# main.net
KiCad netlist of a schematic drawn in EAGLE
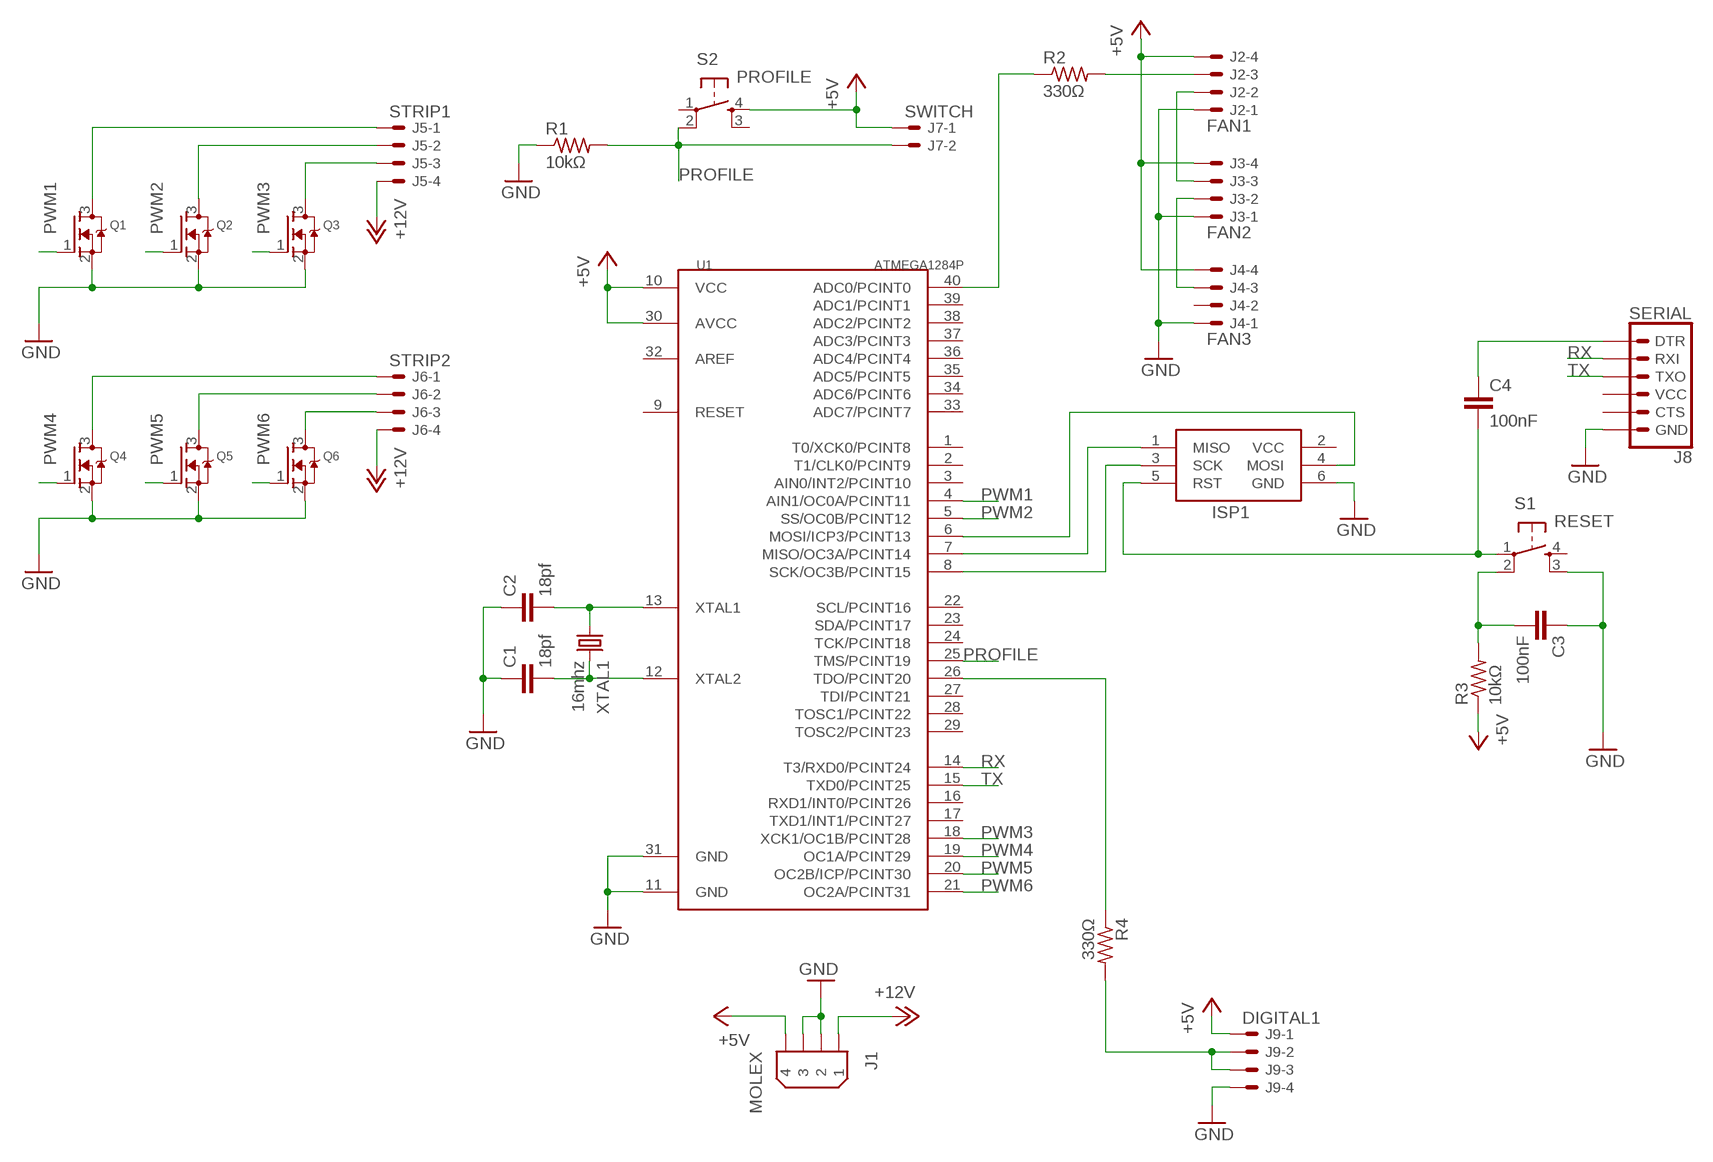
[diagram p0: schematic, sheet 1]

(export (version "E")
  (design (tool "Eeschema 10.0.6"))
  (components
    (comp (ref "C1")
      (value "18pf")
      (footprint "eagle-import:C0805")
      (libsource (lib "eagle-import") (part "C"))
    )
    (comp (ref "C2")
      (value "18pf")
      (footprint "eagle-import:C0805")
      (libsource (lib "eagle-import") (part "C"))
    )
    (comp (ref "C3")
      (value "100nF")
      (footprint "eagle-import:C0805")
      (libsource (lib "eagle-import") (part "C-EUC0805"))
    )
    (comp (ref "C4")
      (value "100nF")
      (footprint "eagle-import:C0805")
      (libsource (lib "eagle-import") (part "C-EUC0805"))
    )
    (comp (ref "ISP1")
      (value "AVRISP-6")
      (footprint "eagle-import:AVRISP")
      (libsource (lib "eagle-import") (part "AVRISP-6"))
    )
    (comp (ref "J1")
      (value "MOLEX")
      (footprint "eagle-import:9090-4R")
      (libsource (lib "eagle-import") (part "9090-4R"))
    )
    (comp (ref "J2")
      (value "FAN1")
      (footprint "eagle-import:22-23-2041")
      (fields (field (name "MF") "MOLEX") (field (name "MPN") "22-23-2041"))
      (libsource (lib "eagle-import") (part "22-23-2041"))
    )
    (comp (ref "J3")
      (value "FAN2")
      (footprint "eagle-import:22-23-2041")
      (fields (field (name "MF") "MOLEX") (field (name "MPN") "22-23-2041"))
      (libsource (lib "eagle-import") (part "22-23-2041"))
    )
    (comp (ref "J4")
      (value "FAN3")
      (footprint "eagle-import:22-23-2041")
      (fields (field (name "MF") "MOLEX") (field (name "MPN") "22-23-2041"))
      (libsource (lib "eagle-import") (part "22-23-2041"))
    )
    (comp (ref "J5")
      (value "STRIP1")
      (footprint "eagle-import:22-23-2041")
      (fields (field (name "MF") "MOLEX") (field (name "MPN") "22-23-2041"))
      (libsource (lib "eagle-import") (part "22-23-2041"))
    )
    (comp (ref "J6")
      (value "STRIP2")
      (footprint "eagle-import:22-23-2041")
      (fields (field (name "MF") "MOLEX") (field (name "MPN") "22-23-2041"))
      (libsource (lib "eagle-import") (part "22-23-2041"))
    )
    (comp (ref "J7")
      (value "SWITCH")
      (footprint "eagle-import:22-23-2021")
      (fields (field (name "MF") "MOLEX") (field (name "MPN") "22-23-2021"))
      (libsource (lib "eagle-import") (part "22-23-2021"))
    )
    (comp (ref "J8")
      (value "SERIAL")
      (footprint "eagle-import:1X06")
      (libsource (lib "eagle-import") (part "6_PIN_SERIAL_TARGET"))
    )
    (comp (ref "J9")
      (value "DIGITAL1")
      (footprint "eagle-import:22-23-2041")
      (fields (field (name "MF") "MOLEX") (field (name "MPN") "22-23-2041"))
      (libsource (lib "eagle-import") (part "22-23-2041"))
    )
    (comp (ref "Q1")
      (value "MOSFET-NREFLOW")
      (footprint "eagle-import:SOT23")
      (libsource (lib "eagle-import") (part "MOSFET-NREFLOW"))
    )
    (comp (ref "Q2")
      (value "MOSFET-NREFLOW")
      (footprint "eagle-import:SOT23")
      (libsource (lib "eagle-import") (part "MOSFET-NREFLOW"))
    )
    (comp (ref "Q3")
      (value "MOSFET-NREFLOW")
      (footprint "eagle-import:SOT23")
      (libsource (lib "eagle-import") (part "MOSFET-NREFLOW"))
    )
    (comp (ref "Q4")
      (value "MOSFET-NREFLOW")
      (footprint "eagle-import:SOT23")
      (libsource (lib "eagle-import") (part "MOSFET-NREFLOW"))
    )
    (comp (ref "Q5")
      (value "MOSFET-NREFLOW")
      (footprint "eagle-import:SOT23")
      (libsource (lib "eagle-import") (part "MOSFET-NREFLOW"))
    )
    (comp (ref "Q6")
      (value "MOSFET-NREFLOW")
      (footprint "eagle-import:SOT23")
      (libsource (lib "eagle-import") (part "MOSFET-NREFLOW"))
    )
    (comp (ref "R1")
      (value "10kΩ")
      (footprint "eagle-import:M0805")
      (libsource (lib "eagle-import") (part "R-US_M0805"))
    )
    (comp (ref "R2")
      (value "330Ω")
      (footprint "eagle-import:M0805")
      (libsource (lib "eagle-import") (part "R-US_M0805"))
    )
    (comp (ref "R3")
      (value "10kΩ")
      (footprint "eagle-import:M0805")
      (libsource (lib "eagle-import") (part "R-US_M0805"))
    )
    (comp (ref "R4")
      (value "330Ω")
      (footprint "eagle-import:M0805")
      (libsource (lib "eagle-import") (part "R-US_M0805"))
    )
    (comp (ref "S1")
      (value "RESET")
      (footprint "eagle-import:B3F-1000")
      (libsource (lib "eagle-import") (part "BUTTON"))
    )
    (comp (ref "S2")
      (value "PROFILE")
      (footprint "eagle-import:B3F-1000")
      (libsource (lib "eagle-import") (part "BUTTON"))
    )
    (comp (ref "U1")
      (value "ATMEGA1284P")
      (footprint "eagle-import:DIL40")
      (libsource (lib "eagle-import") (part "MEGA1284P"))
    )
    (comp (ref "XTAL1")
      (value "16mhz")
      (footprint "eagle-import:HC49U-V")
      (libsource (lib "eagle-import") (part "CRYSTALHC49U-V"))
    )
  )
  (nets
    (net (code "1") (name "+5V") (class "Default")
      (node (ref "J1") (pin "4") (pinfunction "4_4") (pintype "passive"))
      (node (ref "J2") (pin "4") (pinfunction "S_4") (pintype "passive"))
      (node (ref "J3") (pin "4") (pinfunction "S_4") (pintype "passive"))
      (node (ref "J4") (pin "4") (pinfunction "S_4") (pintype "passive"))
      (node (ref "J7") (pin "1") (pinfunction "S_1") (pintype "passive"))
      (node (ref "J9") (pin "1") (pinfunction "S_1") (pintype "passive"))
      (node (ref "R3") (pin "1") (pinfunction "1_1") (pintype "passive"))
      (node (ref "S2") (pin "4") (pinfunction "S_4") (pintype "passive"))
      (node (ref "U1") (pin "10") (pinfunction "VCC_10") (pintype "bidirectional"))
      (node (ref "U1") (pin "30") (pinfunction "AVCC_30") (pintype "bidirectional"))
    )
    (net (code "2") (name "+12V") (class "Default")
      (node (ref "J1") (pin "1") (pinfunction "1_1") (pintype "passive"))
      (node (ref "J5") (pin "4") (pinfunction "S_4") (pintype "passive"))
      (node (ref "J6") (pin "4") (pinfunction "S_4") (pintype "passive"))
    )
    (net (code "3") (name "/PROFILE") (class "Default")
      (node (ref "J7") (pin "2") (pinfunction "S_2") (pintype "passive"))
      (node (ref "R1") (pin "2") (pinfunction "2_2") (pintype "passive"))
      (node (ref "S2") (pin "2") (pinfunction "P1_2") (pintype "passive"))
      (node (ref "U1") (pin "25") (pinfunction "TMS/PCINT19_25") (pintype "bidirectional"))
    )
    (net (code "4") (name "/PWM1") (class "Default")
      (node (ref "Q1") (pin "1") (pinfunction "G_1") (pintype "bidirectional"))
      (node (ref "U1") (pin "4") (pinfunction "AIN1/OC0A/PCINT11_4") (pintype "bidirectional"))
    )
    (net (code "5") (name "/PWM2") (class "Default")
      (node (ref "Q2") (pin "1") (pinfunction "G_1") (pintype "bidirectional"))
      (node (ref "U1") (pin "5") (pinfunction "SS/OC0B/PCINT12_5") (pintype "bidirectional"))
    )
    (net (code "6") (name "/PWM3") (class "Default")
      (node (ref "Q3") (pin "1") (pinfunction "G_1") (pintype "bidirectional"))
      (node (ref "U1") (pin "18") (pinfunction "XCK1/OC1B/PCINT28_18") (pintype "bidirectional"))
    )
    (net (code "7") (name "/PWM4") (class "Default")
      (node (ref "Q4") (pin "1") (pinfunction "G_1") (pintype "bidirectional"))
      (node (ref "U1") (pin "19") (pinfunction "OC1A/PCINT29_19") (pintype "bidirectional"))
    )
    (net (code "8") (name "/PWM5") (class "Default")
      (node (ref "Q5") (pin "1") (pinfunction "G_1") (pintype "bidirectional"))
      (node (ref "U1") (pin "20") (pinfunction "OC2B/ICP/PCINT30_20") (pintype "bidirectional"))
    )
    (net (code "9") (name "/PWM6") (class "Default")
      (node (ref "Q6") (pin "1") (pinfunction "G_1") (pintype "bidirectional"))
      (node (ref "U1") (pin "21") (pinfunction "OC2A/PCINT31_21") (pintype "bidirectional"))
    )
    (net (code "10") (name "/RESET") (class "Default")
      (node (ref "C3") (pin "2") (pinfunction "2_2") (pintype "passive"))
      (node (ref "C4") (pin "2") (pinfunction "2_2") (pintype "passive"))
      (node (ref "ISP1") (pin "5") (pinfunction "RST_5") (pintype "output"))
      (node (ref "R3") (pin "2") (pinfunction "2_2") (pintype "passive"))
      (node (ref "S1") (pin "1") (pinfunction "P_1") (pintype "passive"))
      (node (ref "S1") (pin "2") (pinfunction "P1_2") (pintype "passive"))
    )
    (net (code "11") (name "/RX") (class "Default")
      (node (ref "J8") (pin "2") (pinfunction "RXI_2") (pintype "passive"))
      (node (ref "U1") (pin "14") (pinfunction "T3/RXD0/PCINT24_14") (pintype "bidirectional"))
    )
    (net (code "12") (name "/TX") (class "Default")
      (node (ref "J8") (pin "3") (pinfunction "TXO_3") (pintype "passive"))
      (node (ref "U1") (pin "15") (pinfunction "TXD0/PCINT25_15") (pintype "bidirectional"))
    )
    (net (code "13") (name "/VCC") (class "Default")
      (node (ref "ISP1") (pin "2") (pinfunction "VCC_2") (pintype "power_in"))
    )
    (net (code "14") (name "GND") (class "Default")
      (node (ref "C1") (pin "1") (pinfunction "1_1") (pintype "passive"))
      (node (ref "C2") (pin "1") (pinfunction "1_1") (pintype "passive"))
      (node (ref "C3") (pin "1") (pinfunction "1_1") (pintype "passive"))
      (node (ref "ISP1") (pin "6") (pinfunction "GND_6") (pintype "power_in"))
      (node (ref "J1") (pin "2") (pinfunction "2_2") (pintype "passive"))
      (node (ref "J1") (pin "3") (pinfunction "3_3") (pintype "passive"))
      (node (ref "J2") (pin "1") (pinfunction "S_1") (pintype "passive"))
      (node (ref "J3") (pin "1") (pinfunction "S_1") (pintype "passive"))
      (node (ref "J4") (pin "1") (pinfunction "S_1") (pintype "passive"))
      (node (ref "J8") (pin "6") (pinfunction "GND_6") (pintype "passive"))
      (node (ref "J9") (pin "4") (pinfunction "S_4") (pintype "passive"))
      (node (ref "Q1") (pin "2") (pinfunction "S_2") (pintype "bidirectional"))
      (node (ref "Q2") (pin "2") (pinfunction "S_2") (pintype "bidirectional"))
      (node (ref "Q3") (pin "2") (pinfunction "S_2") (pintype "bidirectional"))
      (node (ref "Q4") (pin "2") (pinfunction "S_2") (pintype "bidirectional"))
      (node (ref "Q5") (pin "2") (pinfunction "S_2") (pintype "bidirectional"))
      (node (ref "Q6") (pin "2") (pinfunction "S_2") (pintype "bidirectional"))
      (node (ref "R1") (pin "1") (pinfunction "1_1") (pintype "passive"))
      (node (ref "S1") (pin "3") (pinfunction "S1_3") (pintype "passive"))
      (node (ref "U1") (pin "11") (pinfunction "GND_11") (pintype "bidirectional"))
      (node (ref "U1") (pin "31") (pinfunction "GND_31") (pintype "bidirectional"))
    )
    (net (code "15") (name "Net-(ISP1-MISO)") (class "Default")
      (node (ref "ISP1") (pin "1") (pinfunction "MISO_1") (pintype "input"))
      (node (ref "U1") (pin "7") (pinfunction "MISO/OC3A/PCINT14_7") (pintype "bidirectional"))
    )
    (net (code "16") (name "Net-(ISP1-MOSI)") (class "Default")
      (node (ref "ISP1") (pin "4") (pinfunction "MOSI_4") (pintype "output"))
      (node (ref "U1") (pin "6") (pinfunction "MOSI/ICP3/PCINT13_6") (pintype "bidirectional"))
    )
    (net (code "17") (name "Net-(ISP1-SCK)") (class "Default")
      (node (ref "ISP1") (pin "3") (pinfunction "SCK_3") (pintype "output"))
      (node (ref "U1") (pin "8") (pinfunction "SCK/OC3B/PCINT15_8") (pintype "bidirectional"))
    )
    (net (code "18") (name "Net-(J2B-S)") (class "Default")
      (node (ref "J2") (pin "2") (pinfunction "S_2") (pintype "passive"))
      (node (ref "J3") (pin "3") (pinfunction "S_3") (pintype "passive"))
    )
    (net (code "19") (name "Net-(J2C-S)") (class "Default")
      (node (ref "J2") (pin "3") (pinfunction "S_3") (pintype "passive"))
      (node (ref "R2") (pin "2") (pinfunction "2_2") (pintype "passive"))
    )
    (net (code "20") (name "Net-(J3B-S)") (class "Default")
      (node (ref "J3") (pin "2") (pinfunction "S_2") (pintype "passive"))
      (node (ref "J4") (pin "3") (pinfunction "S_3") (pintype "passive"))
    )
    (net (code "21") (name "Net-(J5A-S)") (class "Default")
      (node (ref "J5") (pin "1") (pinfunction "S_1") (pintype "passive"))
      (node (ref "Q1") (pin "3") (pinfunction "D_3") (pintype "bidirectional"))
    )
    (net (code "22") (name "Net-(J5B-S)") (class "Default")
      (node (ref "J5") (pin "2") (pinfunction "S_2") (pintype "passive"))
      (node (ref "Q2") (pin "3") (pinfunction "D_3") (pintype "bidirectional"))
    )
    (net (code "23") (name "Net-(J5C-S)") (class "Default")
      (node (ref "J5") (pin "3") (pinfunction "S_3") (pintype "passive"))
      (node (ref "Q3") (pin "3") (pinfunction "D_3") (pintype "bidirectional"))
    )
    (net (code "24") (name "Net-(J6A-S)") (class "Default")
      (node (ref "J6") (pin "1") (pinfunction "S_1") (pintype "passive"))
      (node (ref "Q4") (pin "3") (pinfunction "D_3") (pintype "bidirectional"))
    )
    (net (code "25") (name "Net-(J6B-S)") (class "Default")
      (node (ref "J6") (pin "2") (pinfunction "S_2") (pintype "passive"))
      (node (ref "Q5") (pin "3") (pinfunction "D_3") (pintype "bidirectional"))
    )
    (net (code "26") (name "Net-(J6C-S)") (class "Default")
      (node (ref "J6") (pin "3") (pinfunction "S_3") (pintype "passive"))
      (node (ref "Q6") (pin "3") (pinfunction "D_3") (pintype "bidirectional"))
    )
    (net (code "27") (name "Net-(J8-DTR)") (class "Default")
      (node (ref "C4") (pin "1") (pinfunction "1_1") (pintype "passive"))
      (node (ref "J8") (pin "1") (pinfunction "DTR_1") (pintype "passive"))
    )
    (net (code "28") (name "Net-(J9B-S)") (class "Default")
      (node (ref "J9") (pin "2") (pinfunction "S_2") (pintype "passive"))
      (node (ref "J9") (pin "3") (pinfunction "S_3") (pintype "passive"))
      (node (ref "R4") (pin "2") (pinfunction "2_2") (pintype "passive"))
    )
    (net (code "29") (name "Net-(U1-ADC0{slash}PCINT0)") (class "Default")
      (node (ref "R2") (pin "1") (pinfunction "1_1") (pintype "passive"))
      (node (ref "U1") (pin "40") (pinfunction "ADC0/PCINT0_40") (pintype "bidirectional"))
    )
    (net (code "30") (name "Net-(U1-TDO{slash}PCINT20)") (class "Default")
      (node (ref "R4") (pin "1") (pinfunction "1_1") (pintype "passive"))
      (node (ref "U1") (pin "26") (pinfunction "TDO/PCINT20_26") (pintype "bidirectional"))
    )
    (net (code "31") (name "Net-(U1-XTAL1)") (class "Default")
      (node (ref "C2") (pin "2") (pinfunction "2_2") (pintype "passive"))
      (node (ref "U1") (pin "13") (pinfunction "XTAL1_13") (pintype "bidirectional"))
      (node (ref "XTAL1") (pin "1") (pinfunction "1_1") (pintype "passive"))
    )
    (net (code "32") (name "Net-(U1-XTAL2)") (class "Default")
      (node (ref "C1") (pin "2") (pinfunction "2_2") (pintype "passive"))
      (node (ref "U1") (pin "12") (pinfunction "XTAL2_12") (pintype "bidirectional"))
      (node (ref "XTAL1") (pin "2") (pinfunction "2_2") (pintype "passive"))
    )
    (net (code "33") (name "unconnected-(J4B-S-Pad2)") (class "Default")
      (node (ref "J4") (pin "2") (pinfunction "S_2") (pintype "passive"))
    )
    (net (code "34") (name "unconnected-(J8-CTS-Pad5)") (class "Default")
      (node (ref "J8") (pin "5") (pinfunction "CTS_5") (pintype "passive"))
    )
    (net (code "35") (name "unconnected-(J8-VCC-Pad4)") (class "Default")
      (node (ref "J8") (pin "4") (pinfunction "VCC_4") (pintype "passive"))
    )
    (net (code "36") (name "unconnected-(S1-S-Pad4)") (class "Default")
      (node (ref "S1") (pin "4") (pinfunction "S_4") (pintype "passive"))
    )
    (net (code "37") (name "unconnected-(S2-P-Pad1)") (class "Default")
      (node (ref "S2") (pin "1") (pinfunction "P_1") (pintype "passive"))
    )
    (net (code "38") (name "unconnected-(S2-S1-Pad3)") (class "Default")
      (node (ref "S2") (pin "3") (pinfunction "S1_3") (pintype "passive"))
    )
    (net (code "39") (name "unconnected-(U1-ADC1{slash}PCINT1-Pad39)") (class "Default")
      (node (ref "U1") (pin "39") (pinfunction "ADC1/PCINT1_39") (pintype "bidirectional"))
    )
    (net (code "40") (name "unconnected-(U1-ADC2{slash}PCINT2-Pad38)") (class "Default")
      (node (ref "U1") (pin "38") (pinfunction "ADC2/PCINT2_38") (pintype "bidirectional"))
    )
    (net (code "41") (name "unconnected-(U1-ADC3{slash}PCINT3-Pad37)") (class "Default")
      (node (ref "U1") (pin "37") (pinfunction "ADC3/PCINT3_37") (pintype "bidirectional"))
    )
    (net (code "42") (name "unconnected-(U1-ADC4{slash}PCINT4-Pad36)") (class "Default")
      (node (ref "U1") (pin "36") (pinfunction "ADC4/PCINT4_36") (pintype "bidirectional"))
    )
    (net (code "43") (name "unconnected-(U1-ADC5{slash}PCINT5-Pad35)") (class "Default")
      (node (ref "U1") (pin "35") (pinfunction "ADC5/PCINT5_35") (pintype "bidirectional"))
    )
    (net (code "44") (name "unconnected-(U1-ADC6{slash}PCINT6-Pad34)") (class "Default")
      (node (ref "U1") (pin "34") (pinfunction "ADC6/PCINT6_34") (pintype "bidirectional"))
    )
    (net (code "45") (name "unconnected-(U1-ADC7{slash}PCINT7-Pad33)") (class "Default")
      (node (ref "U1") (pin "33") (pinfunction "ADC7/PCINT7_33") (pintype "bidirectional"))
    )
    (net (code "46") (name "unconnected-(U1-AIN0{slash}INT2{slash}PCINT10-Pad3)") (class "Default")
      (node (ref "U1") (pin "3") (pinfunction "AIN0/INT2/PCINT10_3") (pintype "bidirectional"))
    )
    (net (code "47") (name "unconnected-(U1-AREF-Pad32)") (class "Default")
      (node (ref "U1") (pin "32") (pinfunction "AREF_32") (pintype "bidirectional"))
    )
    (net (code "48") (name "unconnected-(U1-RESET-Pad9)") (class "Default")
      (node (ref "U1") (pin "9") (pinfunction "RESET_9") (pintype "bidirectional"))
    )
    (net (code "49") (name "unconnected-(U1-RXD1{slash}INT0{slash}PCINT26-Pad16)") (class "Default")
      (node (ref "U1") (pin "16") (pinfunction "RXD1/INT0/PCINT26_16") (pintype "bidirectional"))
    )
    (net (code "50") (name "unconnected-(U1-SCL{slash}PCINT16-Pad22)") (class "Default")
      (node (ref "U1") (pin "22") (pinfunction "SCL/PCINT16_22") (pintype "bidirectional"))
    )
    (net (code "51") (name "unconnected-(U1-SDA{slash}PCINT17-Pad23)") (class "Default")
      (node (ref "U1") (pin "23") (pinfunction "SDA/PCINT17_23") (pintype "bidirectional"))
    )
    (net (code "52") (name "unconnected-(U1-T0{slash}XCK0{slash}PCINT8-Pad1)") (class "Default")
      (node (ref "U1") (pin "1") (pinfunction "T0/XCK0/PCINT8_1") (pintype "bidirectional"))
    )
    (net (code "53") (name "unconnected-(U1-T1{slash}CLK0{slash}PCINT9-Pad2)") (class "Default")
      (node (ref "U1") (pin "2") (pinfunction "T1/CLK0/PCINT9_2") (pintype "bidirectional"))
    )
    (net (code "54") (name "unconnected-(U1-TCK{slash}PCINT18-Pad24)") (class "Default")
      (node (ref "U1") (pin "24") (pinfunction "TCK/PCINT18_24") (pintype "bidirectional"))
    )
    (net (code "55") (name "unconnected-(U1-TDI{slash}PCINT21-Pad27)") (class "Default")
      (node (ref "U1") (pin "27") (pinfunction "TDI/PCINT21_27") (pintype "bidirectional"))
    )
    (net (code "56") (name "unconnected-(U1-TOSC1{slash}PCINT22-Pad28)") (class "Default")
      (node (ref "U1") (pin "28") (pinfunction "TOSC1/PCINT22_28") (pintype "bidirectional"))
    )
    (net (code "57") (name "unconnected-(U1-TOSC2{slash}PCINT23-Pad29)") (class "Default")
      (node (ref "U1") (pin "29") (pinfunction "TOSC2/PCINT23_29") (pintype "bidirectional"))
    )
    (net (code "58") (name "unconnected-(U1-TXD1{slash}INT1{slash}PCINT27-Pad17)") (class "Default")
      (node (ref "U1") (pin "17") (pinfunction "TXD1/INT1/PCINT27_17") (pintype "bidirectional"))
    )
  )
)
